# DE-260924.net
KiCad netlist of a schematic drawn in Altium Designer
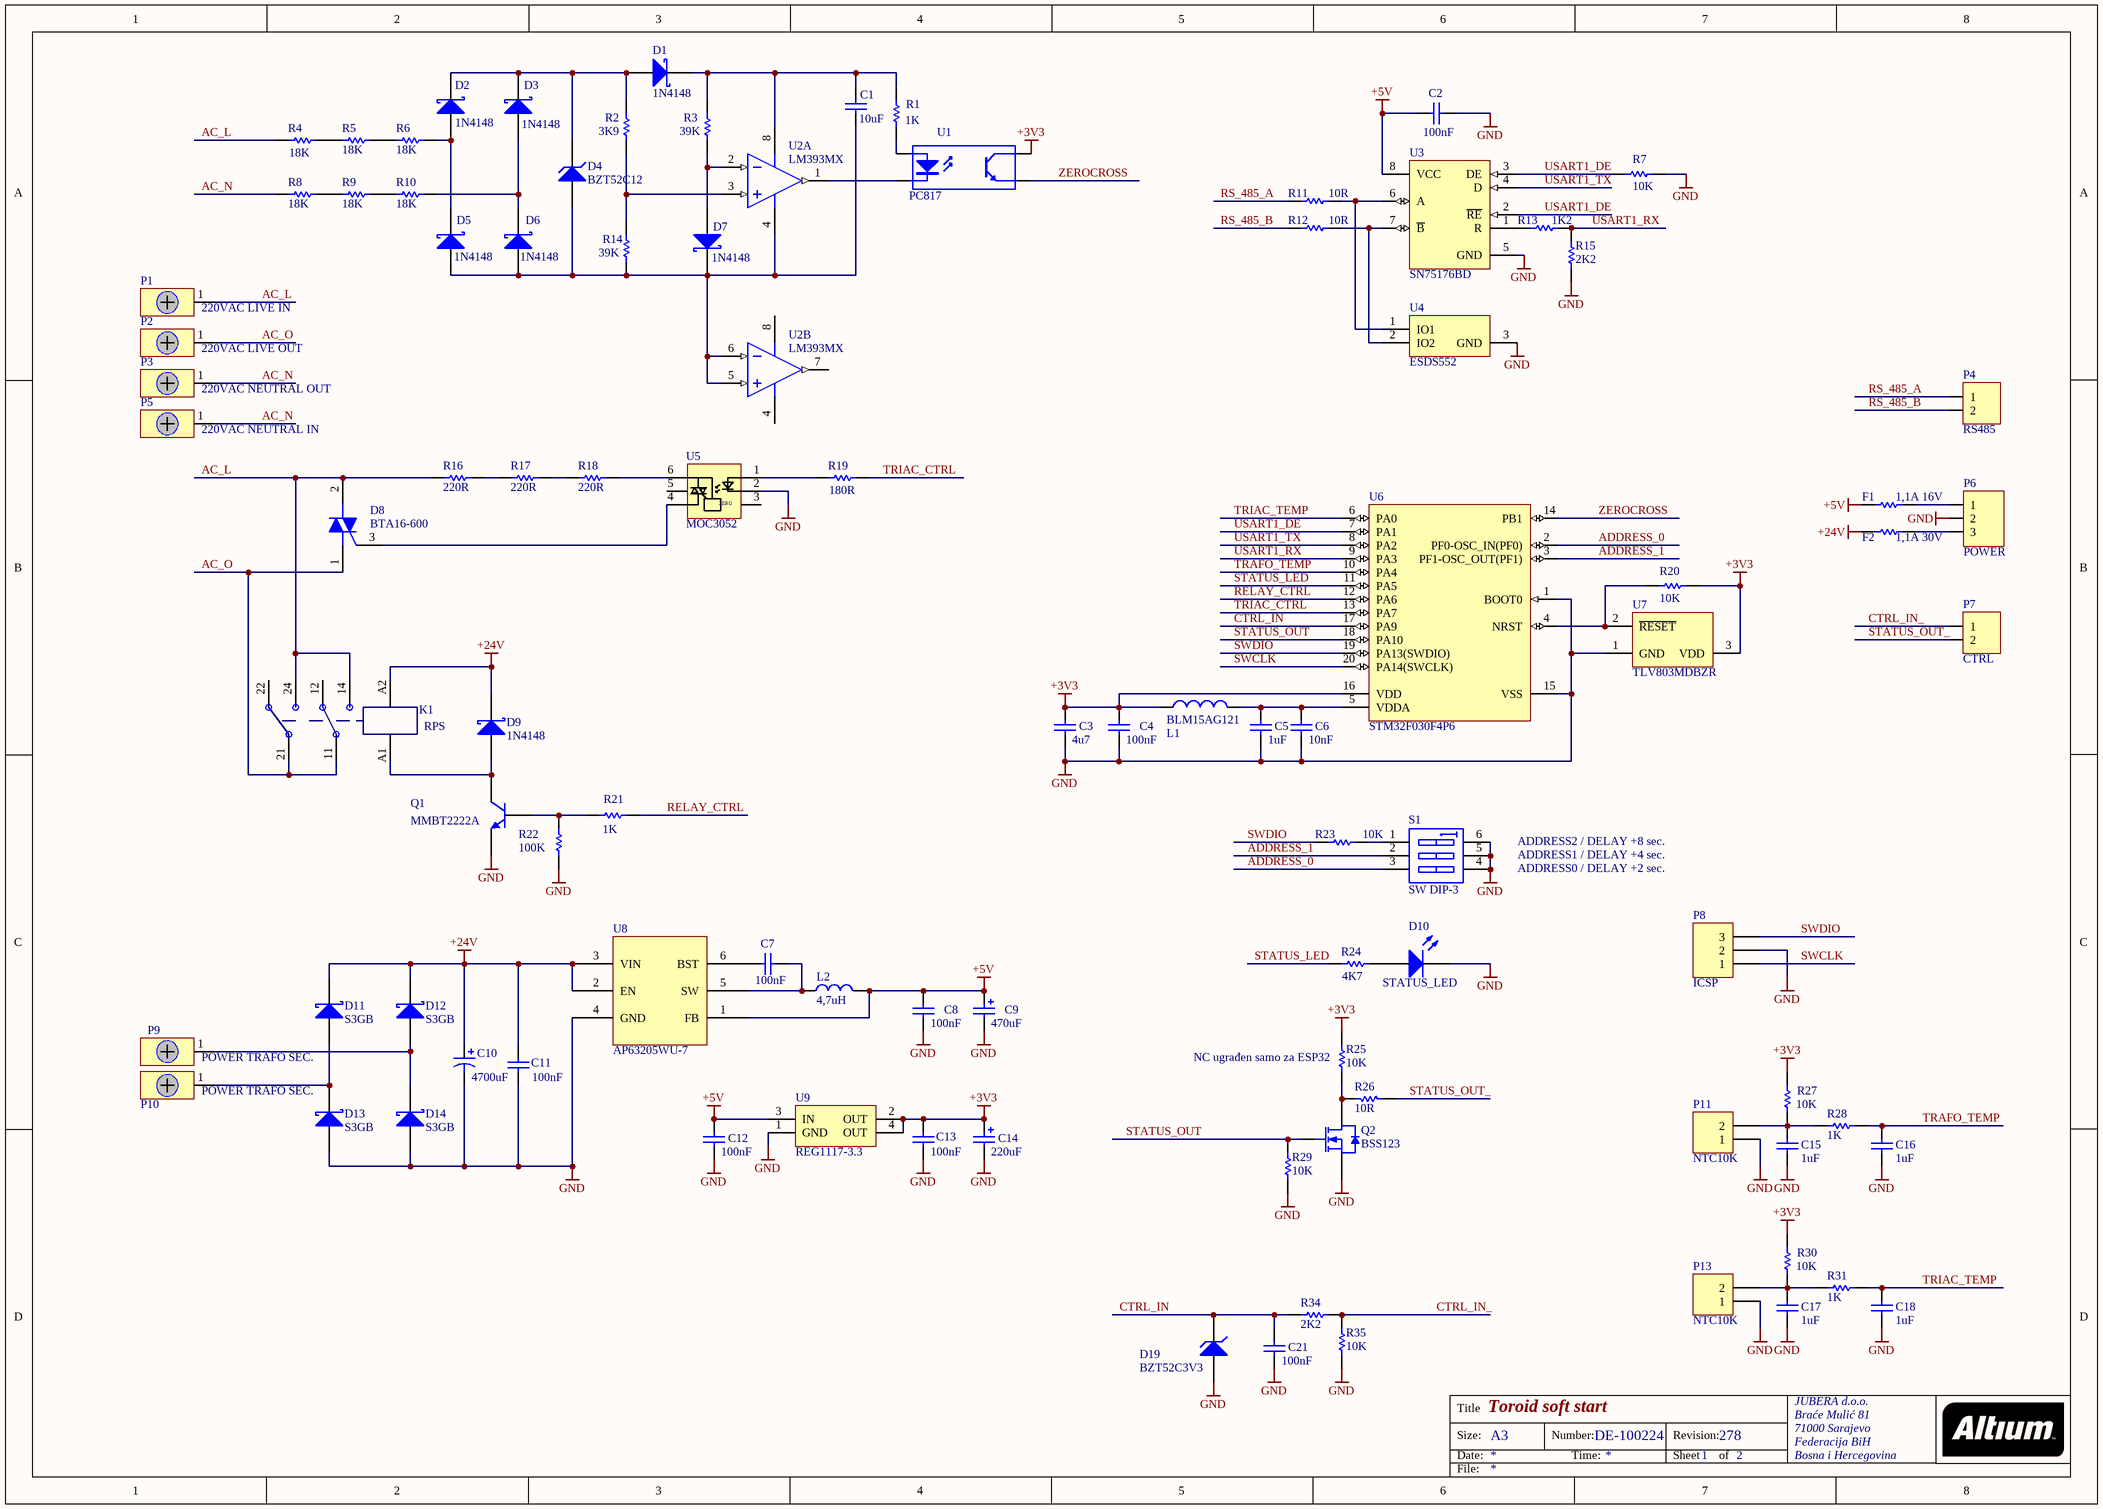
[diagram p0: DE-260924.SchDoc]

(export (version "E")
  (design (tool "Eeschema 10.0.6"))
  (components
    (comp (ref "C1")
      (value "10uF")
      (footprint "0805")
      (description "Ceramic Chip Capacitor - Standard")
      (fields (field (name "PUBLISHER") "Altium Limited"))
      (libsource (lib "DE-260924") (part "C0805"))
    )
    (comp (ref "C2")
      (value "100nF")
      (footprint "0603")
      (description "Ceramic Chip Capacitor - Standard")
      (fields (field (name "PUBLISHER") "Altium Limited"))
      (libsource (lib "DE-260924") (part "C0603"))
    )
    (comp (ref "C3")
      (value "4u7")
      (footprint "0805")
      (description "Ceramic Chip Capacitor - Standard")
      (fields (field (name "Comment") "C0805") (field (name "PUBLISHER") "Altium Limited"))
      (libsource (lib "DE-260924") (part "C0805"))
    )
    (comp (ref "C4")
      (value "100nF")
      (footprint "0603")
      (description "Ceramic Chip Capacitor - Standard")
      (fields (field (name "Comment") "C0603") (field (name "PUBLISHER") "Altium Limited"))
      (libsource (lib "DE-260924") (part "C0603"))
    )
    (comp (ref "C5")
      (value "1uF")
      (footprint "0603")
      (description "Ceramic Chip Capacitor - Standard")
      (fields (field (name "Comment") "C0603") (field (name "PUBLISHER") "Altium Limited"))
      (libsource (lib "DE-260924") (part "C0603"))
    )
    (comp (ref "C6")
      (value "10nF")
      (footprint "0603")
      (description "Ceramic Chip Capacitor - Standard")
      (fields (field (name "Comment") "C0603") (field (name "PUBLISHER") "Altium Limited"))
      (libsource (lib "DE-260924") (part "C0603"))
    )
    (comp (ref "C7")
      (value "100nF")
      (footprint "0603")
      (description "Ceramic Chip Capacitor - 25V")
      (fields (field (name "PUBLISHER") "Altium Limited"))
      (libsource (lib "DE-260924") (part "C0603"))
    )
    (comp (ref "C8")
      (value "100nF")
      (footprint "0603")
      (description "Ceramic Chip Capacitor - 25V")
      (fields (field (name "Comment") "C0603") (field (name "PUBLISHER") "Altium Limited"))
      (libsource (lib "DE-260924") (part "C0603"))
    )
    (comp (ref "C9")
      (value "470uF")
      (footprint "SMD,D6.3xL7.7mm Aluminum Electrolytic Capacitors")
      (description "470uF 16V 185mA@120Hz ±20% SMD,D6.3xL7.7mm Aluminum Electrolytic Capacitors - SMD ROHS")
      (fields (field (name "PUBLISHER") "Altium Limited"))
      (libsource (lib "DE-260924") (part "ROQANG RVT1C471M0607"))
    )
    (comp (ref "C10")
      (value "4700uF")
      (footprint "CAPPR5-13X25")
      (description "Aluminum Electrolytic Capacitor, Radial Style with Long Leads: 4700uF, 10V")
      (fields (field (name "PUBLISHER") "Altium Limited"))
      (libsource (lib "Vishay Roederstein Electrolytic Radial-Lead Capacitor") (part "EKA00GG447C00"))
    )
    (comp (ref "C11")
      (value "100nF")
      (footprint "0603")
      (description "Ceramic Chip Capacitor - Standard")
      (fields (field (name "PUBLISHER") "Altium Limited"))
      (libsource (lib "DE-260924") (part "C0603"))
    )
    (comp (ref "C12")
      (value "100nF")
      (footprint "0603")
      (description "Ceramic Chip Capacitor - 25V")
      (fields (field (name "PUBLISHER") "Altium Limited"))
      (libsource (lib "DE-260924") (part "C0603"))
    )
    (comp (ref "C13")
      (value "100nF")
      (footprint "0603")
      (description "Ceramic Chip Capacitor - Standard")
      (fields (field (name "PUBLISHER") "Altium Limited"))
      (libsource (lib "DE-260924") (part "C0603"))
    )
    (comp (ref "C14")
      (value "220uF")
      (footprint "SMD,D6.3xL7.7mm Aluminum Electrolytic Capacitors")
      (description "220uF 16V 110mA@120Hz ±20% SMD,D6.3xL7.7mm Aluminum Electrolytic Capacitors - SMD ROHS")
      (fields (field (name "PUBLISHER") "Altium Limited"))
      (libsource (lib "DE-260924") (part "ROQANG VT1C221M0607"))
    )
    (comp (ref "C15")
      (value "1uF")
      (footprint "0603")
      (description "Ceramic Chip Capacitor - Standard")
      (fields (field (name "PUBLISHER") "Altium Limited"))
      (libsource (lib "DE-260924") (part "C0603"))
    )
    (comp (ref "C16")
      (value "1uF")
      (footprint "0603")
      (description "Ceramic Chip Capacitor - Standard")
      (fields (field (name "PUBLISHER") "Altium Limited"))
      (libsource (lib "DE-260924") (part "C0603"))
    )
    (comp (ref "C17")
      (value "1uF")
      (footprint "0603")
      (description "Ceramic Chip Capacitor - Standard")
      (fields (field (name "PUBLISHER") "Altium Limited"))
      (libsource (lib "DE-260924") (part "C0603"))
    )
    (comp (ref "C18")
      (value "1uF")
      (footprint "0603")
      (description "Ceramic Chip Capacitor - Standard")
      (fields (field (name "PUBLISHER") "Altium Limited"))
      (libsource (lib "DE-260924") (part "C0603"))
    )
    (comp (ref "C21")
      (value "100nF")
      (footprint "0603")
      (description "Ceramic Chip Capacitor - Standard")
      (fields (field (name "PUBLISHER") "Altium Limited"))
      (libsource (lib "DE-260924") (part "C0603"))
    )
    (comp (ref "D1")
      (value "1N4148")
      (footprint "SOD323")
      (description "Schottky Barrier Diode")
      (fields (field (name "PUBLISHER") "Altium Limited"))
      (libsource (lib "DE-100224") (part "1PS76SB10"))
    )
    (comp (ref "D2")
      (value "1N4148")
      (footprint "SOD323")
      (description "Schottky Barrier Diode")
      (fields (field (name "PUBLISHER") "Altium Limited"))
      (libsource (lib "DE-100224") (part "1PS76SB10"))
    )
    (comp (ref "D3")
      (value "1N4148")
      (footprint "SOD323")
      (description "Schottky Barrier Diode")
      (fields (field (name "PUBLISHER") "Altium Limited"))
      (libsource (lib "DE-100224") (part "1PS76SB10"))
    )
    (comp (ref "D4")
      (value "BZT52C12")
      (footprint "SOD-123")
      (description "Surface Mount Zener Diode")
      (fields (field (name "PUBLISHER") "Altium Limited"))
      (libsource (lib "Vishay Lite-On Discrete Diode") (part "BZT52C12"))
    )
    (comp (ref "D5")
      (value "1N4148")
      (footprint "SOD323")
      (description "Schottky Barrier Diode")
      (fields (field (name "PUBLISHER") "Altium Limited"))
      (libsource (lib "DE-100224") (part "1PS76SB10"))
    )
    (comp (ref "D6")
      (value "1N4148")
      (footprint "SOD323")
      (description "Schottky Barrier Diode")
      (fields (field (name "PUBLISHER") "Altium Limited"))
      (libsource (lib "DE-100224") (part "1PS76SB10"))
    )
    (comp (ref "D7")
      (value "1N4148")
      (footprint "SOD323")
      (description "Schottky Barrier Diode")
      (fields (field (name "PUBLISHER") "Altium Limited"))
      (libsource (lib "DE-100224") (part "1PS76SB10"))
    )
    (comp (ref "D8")
      (value "BTA16-600")
      (footprint "ONSC-TO-220-3-221A-07")
      (description "Triacs, Silicon Bidirectional Thyristor, 3-Pin TO-220, Pb-Free, Tube")
      (fields (field (name "MANUFACTURER") "On Semiconductor") (field (name "PARTNUMBER") "BTA08-600BW3G"))
      (libsource (lib "DE-100224") (part "BTA08-600BW3G"))
    )
    (comp (ref "D9")
      (value "1N4148")
      (footprint "SOD323")
      (description "Schottky Barrier Diode")
      (fields (field (name "PUBLISHER") "Altium Limited"))
      (libsource (lib "DE-100224") (part "1PS76SB10"))
    )
    (comp (ref "D10")
      (value "STATUS_LED")
      (footprint "1.6X0.8X0.8")
      (description "Blue Surface Mount Chip LED, Blue")
      (fields (field (name "PUBLISHER") "Altium Limited"))
      (libsource (lib "DE-160724") (part "HSMB-C190"))
    )
    (comp (ref "D11")
      (value "S3GB")
      (footprint "SMB")
      (description "Schottky Diode")
      (fields (field (name "PUBLISHER") "Altium Limited"))
      (libsource (lib "Miscellaneous Devices") (part "D Schottky"))
    )
    (comp (ref "D12")
      (value "S3GB")
      (footprint "SMB")
      (description "Schottky Diode")
      (fields (field (name "PUBLISHER") "Altium Limited"))
      (libsource (lib "Miscellaneous Devices") (part "D Schottky"))
    )
    (comp (ref "D13")
      (value "S3GB")
      (footprint "SMB")
      (description "Schottky Diode")
      (fields (field (name "PUBLISHER") "Altium Limited"))
      (libsource (lib "Miscellaneous Devices") (part "D Schottky"))
    )
    (comp (ref "D14")
      (value "S3GB")
      (footprint "SMB")
      (description "Schottky Diode")
      (fields (field (name "PUBLISHER") "Altium Limited"))
      (libsource (lib "Miscellaneous Devices") (part "D Schottky"))
    )
    (comp (ref "D19")
      (value "BZT52C3V3")
      (footprint "SOD-123")
      (description "Surface Mount Zener Diode")
      (fields (field (name "PUBLISHER") "Altium Limited"))
      (libsource (lib "Vishay Lite-On Discrete Diode") (part "BZT52C3V3"))
    )
    (comp (ref "F1")
      (value "1,1A 16V")
      (footprint "12-1812")
      (description "Retriggerable SMD fuse 1,1A, 16V")
      (fields (field (name "PUBLISHER") "Altium Limited"))
      (libsource (lib "DE-260924") (part "ERJL12"))
    )
    (comp (ref "F2")
      (value "1,1A 30V")
      (footprint "12-1812")
      (description "Retriggerable SMD fuse 1,1A, 16V")
      (fields (field (name "PUBLISHER") "Altium Limited"))
      (libsource (lib "DE-260924") (part "ERJL12"))
    )
    (comp (ref "K1")
      (value "RPS")
      (footprint "RPS 2CO 8A 24V")
      (libsource (lib "DE-260924") (part "PCB relay 2CO, 8A, 24VDC, RPS serie 5mm"))
    )
    (comp (ref "L1")
      (value "BLM15AG121")
      (footprint "0603")
      (description "SMD chip inductor")
      (fields (field (name "PUBLISHER") "Altium Limited"))
      (libsource (lib "DE-260924") (part "Chip inductor"))
    )
    (comp (ref "L2")
      (value "4,7uH")
      (footprint "XRNR4030-4.7uH/M")
      (libsource (lib "DE-260924") (part "Inductor"))
    )
    (comp (ref "P1")
      (value "220VAC LIVE IN")
      (footprint "WIRE PAD")
      (libsource (lib "DE-260924") (part "Wire Lug"))
    )
    (comp (ref "P2")
      (value "220VAC LIVE OUT")
      (footprint "WIRE PAD")
      (libsource (lib "DE-260924") (part "Wire Lug"))
    )
    (comp (ref "P3")
      (value "220VAC NEUTRAL OUT")
      (footprint "WIRE PAD")
      (libsource (lib "DE-260924") (part "Wire Lug"))
    )
    (comp (ref "P4")
      (value "RS485")
      (footprint "TERMINAL BLOK 2")
      (description "Terminal blok konektor 3,5 mm")
      (libsource (lib "DE-160724") (part "TERMINAL BLOK 2"))
    )
    (comp (ref "P5")
      (value "220VAC NEUTRAL IN")
      (footprint "WIRE PAD")
      (libsource (lib "DE-260924") (part "Wire Lug"))
    )
    (comp (ref "P6")
      (value "POWER")
      (footprint "TERMINAL BLOK 3")
      (description "3 pinski terminal blok konektor")
      (libsource (lib "DE-100224") (part "TERMINAL BLOK 3"))
    )
    (comp (ref "P7")
      (value "CTRL")
      (footprint "TERMINAL BLOK 2")
      (description "Terminal blok konektor 3,5 mm")
      (libsource (lib "DE-160724") (part "TERMINAL BLOK 2"))
    )
    (comp (ref "P8")
      (value "ICSP")
      (footprint "HDR1X3")
      (description "Header, 3-Pin")
      (fields (field (name "PUBLISHER") "Altium Limited"))
      (libsource (lib "Miscellaneous Connectors") (part "Header 3"))
    )
    (comp (ref "P9")
      (value "POWER TRAFO SEC.")
      (footprint "WIRE PAD")
      (libsource (lib "DE-260924") (part "Wire Lug"))
    )
    (comp (ref "P10")
      (value "POWER TRAFO SEC.")
      (footprint "WIRE PAD")
      (libsource (lib "DE-260924") (part "Wire Lug"))
    )
    (comp (ref "P11")
      (value "NTC10K")
      (footprint "HDR1X2")
      (description "Header, 2-Pin")
      (fields (field (name "PUBLISHER") "Altium Limited"))
      (libsource (lib "Miscellaneous Connectors") (part "Header 2"))
    )
    (comp (ref "P13")
      (value "NTC10K")
      (footprint "HDR1X2")
      (description "Header, 2-Pin")
      (fields (field (name "PUBLISHER") "Altium Limited"))
      (libsource (lib "Miscellaneous Connectors") (part "Header 2"))
    )
    (comp (ref "Q1")
      (value "MMBT2222A")
      (footprint "SOT23_N")
      (description "NPN General-purpose Transistor")
      (fields (field (name "PUBLISHER") "Altium Limited"))
      (libsource (lib "DE-100224") (part "BC817"))
    )
    (comp (ref "Q2")
      (value "BSS123")
      (footprint "SOT23_N")
      (description "N-channel Enhancement Mode Vertical D-MOSFET")
      (fields (field (name "PUBLISHER") "Altium Limited"))
      (libsource (lib "DE-260924") (part "BSS123"))
    )
    (comp (ref "R1")
      (value "1K")
      (footprint "ERA-0603")
      (fields (field (name "PUBLISHER") "Altium Limited"))
      (libsource (lib "DE-100224") (part "ERAV"))
    )
    (comp (ref "R2")
      (value "3K9")
      (footprint "ERA-0603")
      (fields (field (name "PUBLISHER") "Altium Limited"))
      (libsource (lib "DE-100224") (part "ERAV"))
    )
    (comp (ref "R3")
      (value "39K")
      (footprint "ERA-0603")
      (fields (field (name "PUBLISHER") "Altium Limited"))
      (libsource (lib "DE-100224") (part "ERAV"))
    )
    (comp (ref "R4")
      (value "18K")
      (footprint "ERA-0805")
      (fields (field (name "Comment") "0805") (field (name "PUBLISHER") "Altium Limited"))
      (libsource (lib "DE-100224") (part "ERAS"))
    )
    (comp (ref "R5")
      (value "18K")
      (footprint "ERA-0805")
      (fields (field (name "PUBLISHER") "Altium Limited"))
      (libsource (lib "DE-100224") (part "ERAS"))
    )
    (comp (ref "R6")
      (value "18K")
      (footprint "ERA-0805")
      (fields (field (name "PUBLISHER") "Altium Limited"))
      (libsource (lib "DE-100224") (part "ERAS"))
    )
    (comp (ref "R7")
      (value "10K")
      (footprint "ERA-0603")
      (fields (field (name "PUBLISHER") "Altium Limited"))
      (libsource (lib "DE-150824") (part "ERAV"))
    )
    (comp (ref "R8")
      (value "18K")
      (footprint "ERA-0805")
      (fields (field (name "PUBLISHER") "Altium Limited"))
      (libsource (lib "DE-100224") (part "ERAS"))
    )
    (comp (ref "R9")
      (value "18K")
      (footprint "ERA-0805")
      (fields (field (name "PUBLISHER") "Altium Limited"))
      (libsource (lib "DE-100224") (part "ERAS"))
    )
    (comp (ref "R10")
      (value "18K")
      (footprint "ERA-0805")
      (fields (field (name "PUBLISHER") "Altium Limited"))
      (libsource (lib "DE-100224") (part "ERAS"))
    )
    (comp (ref "R11")
      (value "10R")
      (footprint "ERA-0805")
      (fields (field (name "PUBLISHER") "Altium Limited"))
      (libsource (lib "DE-150824") (part "ERAS"))
    )
    (comp (ref "R12")
      (value "10R")
      (footprint "ERA-0805")
      (fields (field (name "PUBLISHER") "Altium Limited"))
      (libsource (lib "DE-150824") (part "ERAS"))
    )
    (comp (ref "R13")
      (value "1K2")
      (footprint "ERA-0603")
      (fields (field (name "PUBLISHER") "Altium Limited"))
      (libsource (lib "DE-150824") (part "ERAV"))
    )
    (comp (ref "R14")
      (value "39K")
      (footprint "ERA-0603")
      (fields (field (name "PUBLISHER") "Altium Limited"))
      (libsource (lib "DE-100224") (part "ERAV"))
    )
    (comp (ref "R15")
      (value "2K2")
      (footprint "ERA-0603")
      (fields (field (name "PUBLISHER") "Altium Limited"))
      (libsource (lib "DE-150824") (part "ERAV"))
    )
    (comp (ref "R16")
      (value "220R")
      (footprint "ERA-0805")
      (fields (field (name "PUBLISHER") "Altium Limited"))
      (libsource (lib "DE-100224") (part "ERAS"))
    )
    (comp (ref "R17")
      (value "220R")
      (footprint "ERA-0805")
      (fields (field (name "PUBLISHER") "Altium Limited"))
      (libsource (lib "DE-100224") (part "ERAS"))
    )
    (comp (ref "R18")
      (value "220R")
      (footprint "ERA-0805")
      (fields (field (name "PUBLISHER") "Altium Limited"))
      (libsource (lib "DE-100224") (part "ERAS"))
    )
    (comp (ref "R19")
      (value "180R")
      (footprint "ERA-0603")
      (fields (field (name "PUBLISHER") "Altium Limited"))
      (libsource (lib "DE-100224") (part "ERAV"))
    )
    (comp (ref "R20")
      (value "10K")
      (footprint "ERA-0603")
      (fields (field (name "Comment") "180R") (field (name "PUBLISHER") "Altium Limited"))
      (libsource (lib "DE-100224") (part "ERAV"))
    )
    (comp (ref "R21")
      (value "1K")
      (footprint "ERA-0603")
      (fields (field (name "PUBLISHER") "Altium Limited"))
      (libsource (lib "DE-100224") (part "ERAV"))
    )
    (comp (ref "R22")
      (value "100K")
      (footprint "ERA-0603")
      (fields (field (name "PUBLISHER") "Altium Limited"))
      (libsource (lib "DE-100224") (part "ERAV"))
    )
    (comp (ref "R23")
      (value "10K")
      (footprint "ERA-0603")
      (fields (field (name "Comment") "180R") (field (name "PUBLISHER") "Altium Limited"))
      (libsource (lib "DE-100224") (part "ERAV"))
    )
    (comp (ref "R24")
      (value "4K7")
      (footprint "ERA-0603")
      (fields (field (name "Comment") "180R") (field (name "PUBLISHER") "Altium Limited"))
      (libsource (lib "DE-100224") (part "ERAV"))
    )
    (comp (ref "R25")
      (value "10K")
      (footprint "ERA-0603")
      (fields (field (name "Comment") "180R") (field (name "PUBLISHER") "Altium Limited"))
      (libsource (lib "DE-100224") (part "ERAV"))
    )
    (comp (ref "R26")
      (value "10R")
      (footprint "ERA-0603")
      (fields (field (name "PUBLISHER") "Altium Limited"))
      (libsource (lib "DE-280817") (part "ERA6Y"))
    )
    (comp (ref "R27")
      (value "10K")
      (footprint "ERA-0603")
      (fields (field (name "PUBLISHER") "Altium Limited"))
      (libsource (lib "DE-100224") (part "ERAV"))
    )
    (comp (ref "R28")
      (value "1K")
      (footprint "ERA-0603")
      (fields (field (name "PUBLISHER") "Altium Limited"))
      (libsource (lib "DE-100224") (part "ERAV"))
    )
    (comp (ref "R29")
      (value "10K")
      (footprint "ERA-0603")
      (fields (field (name "Comment") "180R") (field (name "PUBLISHER") "Altium Limited"))
      (libsource (lib "DE-100224") (part "ERAV"))
    )
    (comp (ref "R30")
      (value "10K")
      (footprint "ERA-0603")
      (fields (field (name "PUBLISHER") "Altium Limited"))
      (libsource (lib "DE-100224") (part "ERAV"))
    )
    (comp (ref "R31")
      (value "1K")
      (footprint "ERA-0603")
      (fields (field (name "PUBLISHER") "Altium Limited"))
      (libsource (lib "DE-100224") (part "ERAV"))
    )
    (comp (ref "R34")
      (value "2K2")
      (footprint "ERA-0603")
      (fields (field (name "Comment") "180R") (field (name "PUBLISHER") "Altium Limited"))
      (libsource (lib "DE-100224") (part "ERAV"))
    )
    (comp (ref "R35")
      (value "10K")
      (footprint "ERA-0603")
      (fields (field (name "Comment") "180R") (field (name "PUBLISHER") "Altium Limited"))
      (libsource (lib "DE-100224") (part "ERAV"))
    )
    (comp (ref "S1")
      (value "SW DIP-3")
      (footprint "DIP-6")
      (description "DIP Switch, 3 Position, SPST")
      (fields (field (name "PUBLISHER") "Altium Limited"))
      (libsource (lib "Miscellaneous Devices") (part "SW DIP-3"))
    )
    (comp (ref "U1")
      (value "PC817")
      (footprint "DIP-4")
      (description "4-Pin Phototransistor Optocoupler")
      (fields (field (name "PUBLISHER") "Altium Limited"))
      (libsource (lib "DE-100224") (part "PC817"))
    )
    (comp (ref "U2")
      (value "LM393MX")
      (footprint "M08A_N")
      (description "Low Power Low Offset Voltage Dual Comparator, 8-pin Narrow SOIC")
      (fields (field (name "MANUFACTURER") "National Semiconductor"))
      (libsource (lib "National Semiconductor Comparator") (part "LM393MX"))
    )
    (comp (ref "U3")
      (value "SN75176BD")
      (footprint "D008_N")
      (description "Differential Bus Transceiver")
      (fields (field (name "PUBLISHER") "Altium Limited"))
      (libsource (lib "DE-150824") (part "SN75176BD"))
    )
    (comp (ref "U4")
      (value "ESDS552")
      (footprint "DCK3_N")
      (fields (field (name "MANUFACTURER") "Texas Instruments") (field (name "PARTNUMBER") "TPD2E007DCKR"))
      (libsource (lib "TI Interface ESD EMI Protection") (part "TPD2E007DCKR"))
    )
    (comp (ref "U5")
      (value "MOC3052")
      (footprint "DIP6")
      (description "Zero-Cross Optoisolator Triac Driver")
      (libsource (lib "DE-100224") (part "MOC3081"))
    )
    (comp (ref "U6")
      (value "STM32F030F4P6")
      (footprint "STM-TSSOP20_N")
      (libsource (lib "STMicroelectronics STM32 F0") (part "STM32F030F4P6"))
    )
    (comp (ref "U7")
      (value "TLV803MDBZR")
      (footprint "DBZ3_N")
      (fields (field (name "MANUFACTURER") "Texas Instruments"))
      (libsource (lib "TI Power Management Supervisor and Reset IC") (part "TLV803MDBZR"))
    )
    (comp (ref "U8")
      (value "AP63205WU-7")
      (footprint "TSOT-26")
      (description "2A synchronous  buck converter")
      (libsource (lib "DE-250624") (part "AP63200"))
    )
    (comp (ref "U9")
      (value "REG1117-3.3")
      (footprint "ZZ311")
      (description "800mA and 1A Low Dropout Positive Regulator 2.85V, 3.3V, 5V, and Adjustable")
      (fields (field (name "PUBLISHER") "Altium Limited"))
      (libsource (lib "DE-251215") (part "REG1117-3.3"))
    )
  )
  (nets
    (net (code "1") (name "+3V3") (class "Default")
      (node (ref "C13") (pin "2") (pinfunction "2_2") (pintype "passive"))
      (node (ref "C14") (pin "1") (pinfunction "1_1") (pintype "passive"))
      (node (ref "C3") (pin "2") (pinfunction "2_2") (pintype "passive"))
      (node (ref "C4") (pin "2") (pinfunction "2_2") (pintype "passive"))
      (node (ref "L1") (pin "1") (pinfunction "1_1") (pintype "passive"))
      (node (ref "R20") (pin "1") (pinfunction "1_1") (pintype "passive"))
      (node (ref "R25") (pin "1") (pinfunction "1_1") (pintype "passive"))
      (node (ref "R27") (pin "2") (pinfunction "2_2") (pintype "passive"))
      (node (ref "R30") (pin "2") (pinfunction "2_2") (pintype "passive"))
      (node (ref "U1") (pin "4") (pinfunction "C_4") (pintype "passive"))
      (node (ref "U6") (pin "16") (pinfunction "VDD_16") (pintype "power_in"))
      (node (ref "U7") (pin "3") (pinfunction "VDD_3") (pintype "power_in"))
      (node (ref "U9") (pin "2") (pinfunction "OUT_2") (pintype "power_in"))
      (node (ref "U9") (pin "4") (pinfunction "OUT_4") (pintype "power_in"))
    )
    (net (code "2") (name "+5V") (class "Default")
      (node (ref "C12") (pin "2") (pinfunction "2_2") (pintype "passive"))
      (node (ref "C2") (pin "2") (pinfunction "2_2") (pintype "passive"))
      (node (ref "C8") (pin "2") (pinfunction "2_2") (pintype "passive"))
      (node (ref "C9") (pin "1") (pinfunction "1_1") (pintype "passive"))
      (node (ref "F1") (pin "1") (pinfunction "1_1") (pintype "passive"))
      (node (ref "L2") (pin "1") (pinfunction "1_1") (pintype "passive"))
      (node (ref "U3") (pin "8") (pinfunction "VCC_8") (pintype "power_in"))
      (node (ref "U8") (pin "1") (pinfunction "FB_1") (pintype "passive"))
      (node (ref "U9") (pin "3") (pinfunction "IN_3") (pintype "power_in"))
    )
    (net (code "3") (name "+24V") (class "Default")
      (node (ref "C10") (pin "1") (pinfunction "1_1") (pintype "passive"))
      (node (ref "C11") (pin "2") (pinfunction "2_2") (pintype "passive"))
      (node (ref "D11") (pin "2") (pinfunction "K_2") (pintype "passive"))
      (node (ref "D12") (pin "2") (pinfunction "K_2") (pintype "passive"))
      (node (ref "D9") (pin "1") (pinfunction "K_1") (pintype "passive"))
      (node (ref "F2") (pin "1") (pinfunction "1_1") (pintype "passive"))
      (node (ref "K1") (pin "A2") (pinfunction "2_A2") (pintype "passive"))
      (node (ref "U8") (pin "2") (pinfunction "EN_2") (pintype "passive"))
      (node (ref "U8") (pin "3") (pinfunction "VIN_3") (pintype "power_in"))
    )
    (net (code "4") (name "/AC_L") (class "Default")
      (node (ref "D8") (pin "2") (pinfunction "MT2_2") (pintype "passive"))
      (node (ref "K1") (pin "14") (pinfunction "4_14") (pintype "passive"))
      (node (ref "K1") (pin "24") (pinfunction "4_24") (pintype "passive"))
      (node (ref "P1") (pin "1") (pinfunction "1_1") (pintype "passive"))
      (node (ref "R16") (pin "1") (pinfunction "1_1") (pintype "passive"))
      (node (ref "R4") (pin "1") (pinfunction "1_1") (pintype "passive"))
    )
    (net (code "5") (name "/AC_N") (class "Default")
      (node (ref "P3") (pin "1") (pinfunction "1_1") (pintype "passive"))
      (node (ref "P5") (pin "1") (pinfunction "1_1") (pintype "passive"))
      (node (ref "R8") (pin "1") (pinfunction "1_1") (pintype "passive"))
    )
    (net (code "6") (name "/AC_O") (class "Default")
      (node (ref "D8") (pin "1") (pinfunction "MT1_1") (pintype "passive"))
      (node (ref "K1") (pin "11") (pinfunction "3_11") (pintype "passive"))
      (node (ref "K1") (pin "21") (pinfunction "3_21") (pintype "passive"))
      (node (ref "P2") (pin "1") (pinfunction "1_1") (pintype "passive"))
    )
    (net (code "7") (name "/ADDRESS_0") (class "Default")
      (node (ref "S1") (pin "3") (pinfunction "A3_3") (pintype "passive"))
      (node (ref "U6") (pin "2") (pinfunction "PF0-OSC_IN(PF0)_2") (pintype "bidirectional"))
    )
    (net (code "8") (name "/ADDRESS_1") (class "Default")
      (node (ref "S1") (pin "2") (pinfunction "A2_2") (pintype "passive"))
      (node (ref "U6") (pin "3") (pinfunction "PF1-OSC_OUT(PF1)_3") (pintype "bidirectional"))
    )
    (net (code "9") (name "/CTRL_IN") (class "Default")
      (node (ref "C21") (pin "2") (pinfunction "2_2") (pintype "passive"))
      (node (ref "D19") (pin "2") (pinfunction "K_2") (pintype "passive"))
      (node (ref "R34") (pin "1") (pinfunction "1_1") (pintype "passive"))
      (node (ref "U6") (pin "17") (pinfunction "PA9_17") (pintype "bidirectional"))
    )
    (net (code "10") (name "/CTRL_IN_") (class "Default")
      (node (ref "P7") (pin "1") (pinfunction "1_1") (pintype "passive"))
      (node (ref "R34") (pin "2") (pinfunction "2_2") (pintype "passive"))
      (node (ref "R35") (pin "1") (pinfunction "1_1") (pintype "passive"))
    )
    (net (code "11") (name "/RELAY_CTRL") (class "Default")
      (node (ref "R21") (pin "1") (pinfunction "1_1") (pintype "passive"))
      (node (ref "U6") (pin "12") (pinfunction "PA6_12") (pintype "bidirectional"))
    )
    (net (code "12") (name "/RS_485_A") (class "Default")
      (node (ref "P4") (pin "1") (pinfunction "1_1") (pintype "passive"))
      (node (ref "R11") (pin "1") (pinfunction "1_1") (pintype "passive"))
    )
    (net (code "13") (name "/RS_485_B") (class "Default")
      (node (ref "P4") (pin "2") (pinfunction "2_2") (pintype "passive"))
      (node (ref "R12") (pin "1") (pinfunction "1_1") (pintype "passive"))
    )
    (net (code "14") (name "/STATUS_LED") (class "Default")
      (node (ref "R24") (pin "2") (pinfunction "2_2") (pintype "passive"))
      (node (ref "U6") (pin "11") (pinfunction "PA5_11") (pintype "bidirectional"))
    )
    (net (code "15") (name "/STATUS_OUT") (class "Default")
      (node (ref "Q2") (pin "1") (pinfunction "G_1") (pintype "passive"))
      (node (ref "R29") (pin "1") (pinfunction "1_1") (pintype "passive"))
      (node (ref "U6") (pin "18") (pinfunction "PA10_18") (pintype "bidirectional"))
    )
    (net (code "16") (name "/STATUS_OUT_") (class "Default")
      (node (ref "P7") (pin "2") (pinfunction "2_2") (pintype "passive"))
      (node (ref "R26") (pin "2") (pinfunction "2_2") (pintype "passive"))
    )
    (net (code "17") (name "/SWCLK") (class "Default")
      (node (ref "P8") (pin "1") (pinfunction "1_1") (pintype "passive"))
      (node (ref "U6") (pin "20") (pinfunction "PA14(SWCLK)_20") (pintype "bidirectional"))
    )
    (net (code "18") (name "/SWDIO") (class "Default")
      (node (ref "P8") (pin "3") (pinfunction "3_3") (pintype "passive"))
      (node (ref "R23") (pin "2") (pinfunction "2_2") (pintype "passive"))
      (node (ref "U6") (pin "19") (pinfunction "PA13(SWDIO)_19") (pintype "bidirectional"))
    )
    (net (code "19") (name "/TRAFO_TEMP") (class "Default")
      (node (ref "C16") (pin "1") (pinfunction "1_1") (pintype "passive"))
      (node (ref "R28") (pin "1") (pinfunction "1_1") (pintype "passive"))
      (node (ref "U6") (pin "10") (pinfunction "PA4_10") (pintype "bidirectional"))
    )
    (net (code "20") (name "/TRIAC_CTRL") (class "Default")
      (node (ref "R19") (pin "1") (pinfunction "1_1") (pintype "passive"))
      (node (ref "U6") (pin "13") (pinfunction "PA7_13") (pintype "bidirectional"))
    )
    (net (code "21") (name "/TRIAC_TEMP") (class "Default")
      (node (ref "C18") (pin "1") (pinfunction "1_1") (pintype "passive"))
      (node (ref "R31") (pin "1") (pinfunction "1_1") (pintype "passive"))
      (node (ref "U6") (pin "6") (pinfunction "PA0_6") (pintype "bidirectional"))
    )
    (net (code "22") (name "/USART1_DE") (class "Default")
      (node (ref "R7") (pin "1") (pinfunction "1_1") (pintype "passive"))
      (node (ref "U3") (pin "2") (pinfunction "~{RE}_2") (pintype "input"))
      (node (ref "U3") (pin "3") (pinfunction "DE_3") (pintype "input"))
      (node (ref "U6") (pin "7") (pinfunction "PA1_7") (pintype "bidirectional"))
    )
    (net (code "23") (name "/USART1_RX") (class "Default")
      (node (ref "R13") (pin "2") (pinfunction "2_2") (pintype "passive"))
      (node (ref "R15") (pin "2") (pinfunction "2_2") (pintype "passive"))
      (node (ref "U6") (pin "9") (pinfunction "PA3_9") (pintype "bidirectional"))
    )
    (net (code "24") (name "/USART1_TX") (class "Default")
      (node (ref "U3") (pin "4") (pinfunction "D_4") (pintype "input"))
      (node (ref "U6") (pin "8") (pinfunction "PA2_8") (pintype "bidirectional"))
    )
    (net (code "25") (name "/ZEROCROSS") (class "Default")
      (node (ref "U1") (pin "3") (pinfunction "E_3") (pintype "passive"))
      (node (ref "U6") (pin "14") (pinfunction "PB1_14") (pintype "bidirectional"))
    )
    (net (code "26") (name "GND") (class "Default")
      (node (ref "C10") (pin "2") (pinfunction "2_2") (pintype "passive"))
      (node (ref "C11") (pin "1") (pinfunction "1_1") (pintype "passive"))
      (node (ref "C12") (pin "1") (pinfunction "1_1") (pintype "passive"))
      (node (ref "C13") (pin "1") (pinfunction "1_1") (pintype "passive"))
      (node (ref "C14") (pin "2") (pinfunction "2_2") (pintype "passive"))
      (node (ref "C15") (pin "2") (pinfunction "2_2") (pintype "passive"))
      (node (ref "C16") (pin "2") (pinfunction "2_2") (pintype "passive"))
      (node (ref "C17") (pin "2") (pinfunction "2_2") (pintype "passive"))
      (node (ref "C18") (pin "2") (pinfunction "2_2") (pintype "passive"))
      (node (ref "C2") (pin "1") (pinfunction "1_1") (pintype "passive"))
      (node (ref "C21") (pin "1") (pinfunction "1_1") (pintype "passive"))
      (node (ref "C3") (pin "1") (pinfunction "1_1") (pintype "passive"))
      (node (ref "C4") (pin "1") (pinfunction "1_1") (pintype "passive"))
      (node (ref "C5") (pin "1") (pinfunction "1_1") (pintype "passive"))
      (node (ref "C6") (pin "1") (pinfunction "1_1") (pintype "passive"))
      (node (ref "C8") (pin "1") (pinfunction "1_1") (pintype "passive"))
      (node (ref "C9") (pin "2") (pinfunction "2_2") (pintype "passive"))
      (node (ref "D10") (pin "2") (pinfunction "K_2") (pintype "passive"))
      (node (ref "D13") (pin "1") (pinfunction "A_1") (pintype "passive"))
      (node (ref "D14") (pin "1") (pinfunction "A_1") (pintype "passive"))
      (node (ref "D19") (pin "1") (pinfunction "A_1") (pintype "passive"))
      (node (ref "P11") (pin "1") (pinfunction "1_1") (pintype "passive"))
      (node (ref "P13") (pin "1") (pinfunction "1_1") (pintype "passive"))
      (node (ref "P6") (pin "2") (pinfunction "2_2") (pintype "passive"))
      (node (ref "P8") (pin "2") (pinfunction "2_2") (pintype "passive"))
      (node (ref "Q1") (pin "2") (pinfunction "E_2") (pintype "passive"))
      (node (ref "Q2") (pin "2") (pinfunction "S_2") (pintype "passive"))
      (node (ref "R15") (pin "1") (pinfunction "1_1") (pintype "passive"))
      (node (ref "R22") (pin "1") (pinfunction "1_1") (pintype "passive"))
      (node (ref "R29") (pin "2") (pinfunction "2_2") (pintype "passive"))
      (node (ref "R35") (pin "2") (pinfunction "2_2") (pintype "passive"))
      (node (ref "R7") (pin "2") (pinfunction "2_2") (pintype "passive"))
      (node (ref "S1") (pin "4") (pinfunction "B3_4") (pintype "passive"))
      (node (ref "S1") (pin "5") (pinfunction "B2_5") (pintype "passive"))
      (node (ref "S1") (pin "6") (pinfunction "B1_6") (pintype "passive"))
      (node (ref "U3") (pin "5") (pinfunction "GND_5") (pintype "power_in"))
      (node (ref "U4") (pin "3") (pinfunction "GND_3") (pintype "power_in"))
      (node (ref "U5") (pin "2") (pinfunction "2_2") (pintype "passive"))
      (node (ref "U6") (pin "1") (pinfunction "BOOT0_1") (pintype "input"))
      (node (ref "U6") (pin "15") (pinfunction "VSS_15") (pintype "power_in"))
      (node (ref "U7") (pin "1") (pinfunction "GND_1") (pintype "power_in"))
      (node (ref "U8") (pin "4") (pinfunction "GND_4") (pintype "power_in"))
      (node (ref "U9") (pin "1") (pinfunction "GND_1") (pintype "power_in"))
    )
    (net (code "27") (name "Net-(C15-Pad1)") (class "Default")
      (node (ref "C15") (pin "1") (pinfunction "1_1") (pintype "passive"))
      (node (ref "P11") (pin "2") (pinfunction "2_2") (pintype "passive"))
      (node (ref "R27") (pin "1") (pinfunction "1_1") (pintype "passive"))
      (node (ref "R28") (pin "2") (pinfunction "2_2") (pintype "passive"))
    )
    (net (code "28") (name "Net-(C17-Pad1)") (class "Default")
      (node (ref "C17") (pin "1") (pinfunction "1_1") (pintype "passive"))
      (node (ref "P13") (pin "2") (pinfunction "2_2") (pintype "passive"))
      (node (ref "R30") (pin "1") (pinfunction "1_1") (pintype "passive"))
      (node (ref "R31") (pin "2") (pinfunction "2_2") (pintype "passive"))
    )
    (net (code "29") (name "Net-(D1-A)") (class "Default")
      (node (ref "D1") (pin "2") (pinfunction "A_2") (pintype "passive"))
      (node (ref "D2") (pin "1") (pinfunction "K_1") (pintype "passive"))
      (node (ref "D3") (pin "1") (pinfunction "K_1") (pintype "passive"))
      (node (ref "D4") (pin "2") (pinfunction "K_2") (pintype "passive"))
      (node (ref "R2") (pin "2") (pinfunction "2_2") (pintype "passive"))
    )
    (net (code "30") (name "Net-(D1-K)") (class "Default")
      (node (ref "C1") (pin "2") (pinfunction "2_2") (pintype "passive"))
      (node (ref "D1") (pin "1") (pinfunction "K_1") (pintype "passive"))
      (node (ref "R1") (pin "2") (pinfunction "2_2") (pintype "passive"))
      (node (ref "R3") (pin "2") (pinfunction "2_2") (pintype "passive"))
      (node (ref "U2") (pin "8") (pinfunction "V+_8") (pintype "power_in"))
    )
    (net (code "31") (name "Net-(D2-A)") (class "Default")
      (node (ref "D2") (pin "2") (pinfunction "A_2") (pintype "passive"))
      (node (ref "D5") (pin "1") (pinfunction "K_1") (pintype "passive"))
      (node (ref "R6") (pin "2") (pinfunction "2_2") (pintype "passive"))
    )
    (net (code "32") (name "Net-(D3-A)") (class "Default")
      (node (ref "D3") (pin "2") (pinfunction "A_2") (pintype "passive"))
      (node (ref "D6") (pin "1") (pinfunction "K_1") (pintype "passive"))
      (node (ref "R10") (pin "2") (pinfunction "2_2") (pintype "passive"))
    )
    (net (code "33") (name "Net-(D4-A)") (class "Default")
      (node (ref "C1") (pin "1") (pinfunction "1_1") (pintype "passive"))
      (node (ref "D4") (pin "1") (pinfunction "A_1") (pintype "passive"))
      (node (ref "D5") (pin "2") (pinfunction "A_2") (pintype "passive"))
      (node (ref "D6") (pin "2") (pinfunction "A_2") (pintype "passive"))
      (node (ref "D7") (pin "1") (pinfunction "K_1") (pintype "passive"))
      (node (ref "R14") (pin "1") (pinfunction "1_1") (pintype "passive"))
      (node (ref "U2") (pin "4") (pinfunction "GND_4") (pintype "power_in"))
      (node (ref "U2") (pin "5") (pinfunction "INB+_5") (pintype "input"))
      (node (ref "U2") (pin "6") (pinfunction "INB-_6") (pintype "input"))
    )
    (net (code "34") (name "Net-(D7-A)") (class "Default")
      (node (ref "D7") (pin "2") (pinfunction "A_2") (pintype "passive"))
      (node (ref "R3") (pin "1") (pinfunction "1_1") (pintype "passive"))
      (node (ref "U2") (pin "2") (pinfunction "INA-_2") (pintype "input"))
    )
    (net (code "35") (name "Net-(D8-G)") (class "Default")
      (node (ref "D8") (pin "3") (pinfunction "G_3") (pintype "passive"))
      (node (ref "U5") (pin "4") (pinfunction "4_4") (pintype "passive"))
    )
    (net (code "36") (name "Net-(D9-A)") (class "Default")
      (node (ref "D9") (pin "2") (pinfunction "A_2") (pintype "passive"))
      (node (ref "K1") (pin "A1") (pinfunction "1_A1") (pintype "passive"))
      (node (ref "Q1") (pin "3") (pinfunction "C_3") (pintype "passive"))
    )
    (net (code "37") (name "Net-(D10-A)") (class "Default")
      (node (ref "D10") (pin "1") (pinfunction "A_1") (pintype "passive"))
      (node (ref "R24") (pin "1") (pinfunction "1_1") (pintype "passive"))
    )
    (net (code "38") (name "Net-(D11-A)") (class "Default")
      (node (ref "D11") (pin "1") (pinfunction "A_1") (pintype "passive"))
      (node (ref "D13") (pin "2") (pinfunction "K_2") (pintype "passive"))
      (node (ref "P10") (pin "1") (pinfunction "1_1") (pintype "passive"))
    )
    (net (code "39") (name "Net-(D12-A)") (class "Default")
      (node (ref "D12") (pin "1") (pinfunction "A_1") (pintype "passive"))
      (node (ref "D14") (pin "2") (pinfunction "K_2") (pintype "passive"))
      (node (ref "P9") (pin "1") (pinfunction "1_1") (pintype "passive"))
    )
    (net (code "40") (name "Net-(F1-Pad2)") (class "Default")
      (node (ref "F1") (pin "2") (pinfunction "2_2") (pintype "passive"))
      (node (ref "P6") (pin "1") (pinfunction "1_1") (pintype "passive"))
    )
    (net (code "41") (name "Net-(F2-Pad2)") (class "Default")
      (node (ref "F2") (pin "2") (pinfunction "2_2") (pintype "passive"))
      (node (ref "P6") (pin "3") (pinfunction "3_3") (pintype "passive"))
    )
    (net (code "42") (name "Net-(Q1-B)") (class "Default")
      (node (ref "Q1") (pin "1") (pinfunction "B_1") (pintype "passive"))
      (node (ref "R21") (pin "2") (pinfunction "2_2") (pintype "passive"))
      (node (ref "R22") (pin "2") (pinfunction "2_2") (pintype "passive"))
    )
    (net (code "43") (name "Net-(Q2-D)") (class "Default")
      (node (ref "Q2") (pin "3") (pinfunction "D_3") (pintype "passive"))
      (node (ref "R25") (pin "2") (pinfunction "2_2") (pintype "passive"))
      (node (ref "R26") (pin "1") (pinfunction "1_1") (pintype "passive"))
    )
    (net (code "44") (name "Net-(R4-Pad2)") (class "Default")
      (node (ref "R4") (pin "2") (pinfunction "2_2") (pintype "passive"))
      (node (ref "R5") (pin "1") (pinfunction "1_1") (pintype "passive"))
    )
    (net (code "45") (name "Net-(R5-Pad2)") (class "Default")
      (node (ref "R5") (pin "2") (pinfunction "2_2") (pintype "passive"))
      (node (ref "R6") (pin "1") (pinfunction "1_1") (pintype "passive"))
    )
    (net (code "46") (name "Net-(R8-Pad2)") (class "Default")
      (node (ref "R8") (pin "2") (pinfunction "2_2") (pintype "passive"))
      (node (ref "R9") (pin "1") (pinfunction "1_1") (pintype "passive"))
    )
    (net (code "47") (name "Net-(R10-Pad1)") (class "Default")
      (node (ref "R10") (pin "1") (pinfunction "1_1") (pintype "passive"))
      (node (ref "R9") (pin "2") (pinfunction "2_2") (pintype "passive"))
    )
    (net (code "48") (name "Net-(R16-Pad2)") (class "Default")
      (node (ref "R16") (pin "2") (pinfunction "2_2") (pintype "passive"))
      (node (ref "R17") (pin "1") (pinfunction "1_1") (pintype "passive"))
    )
    (net (code "49") (name "Net-(R17-Pad2)") (class "Default")
      (node (ref "R17") (pin "2") (pinfunction "2_2") (pintype "passive"))
      (node (ref "R18") (pin "1") (pinfunction "1_1") (pintype "passive"))
    )
    (net (code "50") (name "Net-(R18-Pad2)") (class "Default")
      (node (ref "R18") (pin "2") (pinfunction "2_2") (pintype "passive"))
      (node (ref "U5") (pin "6") (pinfunction "6_6") (pintype "passive"))
    )
    (net (code "51") (name "Net-(R19-Pad2)") (class "Default")
      (node (ref "R19") (pin "2") (pinfunction "2_2") (pintype "passive"))
      (node (ref "U5") (pin "1") (pinfunction "1_1") (pintype "passive"))
    )
    (net (code "52") (name "Net-(S1-A1)") (class "Default")
      (node (ref "R23") (pin "1") (pinfunction "1_1") (pintype "passive"))
      (node (ref "S1") (pin "1") (pinfunction "A1_1") (pintype "passive"))
    )
    (net (code "53") (name "Net-(U1-A)") (class "Default")
      (node (ref "R1") (pin "1") (pinfunction "1_1") (pintype "passive"))
      (node (ref "U1") (pin "1") (pinfunction "A_1") (pintype "passive"))
    )
    (net (code "54") (name "Net-(U1-K)") (class "Default")
      (node (ref "U1") (pin "2") (pinfunction "K_2") (pintype "passive"))
      (node (ref "U2") (pin "1") (pinfunction "OUTA_1") (pintype "output"))
    )
    (net (code "55") (name "Net-(U2A-INA+)") (class "Default")
      (node (ref "R14") (pin "2") (pinfunction "2_2") (pintype "passive"))
      (node (ref "R2") (pin "1") (pinfunction "1_1") (pintype "passive"))
      (node (ref "U2") (pin "3") (pinfunction "INA+_3") (pintype "input"))
    )
    (net (code "56") (name "Net-(U3-A)") (class "Default")
      (node (ref "R11") (pin "2") (pinfunction "2_2") (pintype "passive"))
      (node (ref "U3") (pin "6") (pinfunction "A_6") (pintype "bidirectional"))
      (node (ref "U4") (pin "1") (pinfunction "IO1_1") (pintype "passive"))
    )
    (net (code "57") (name "Net-(U3-R)") (class "Default")
      (node (ref "R13") (pin "1") (pinfunction "1_1") (pintype "passive"))
      (node (ref "U3") (pin "1") (pinfunction "R_1") (pintype "tri_state"))
    )
    (net (code "58") (name "Net-(U3-~{B})") (class "Default")
      (node (ref "R12") (pin "2") (pinfunction "2_2") (pintype "passive"))
      (node (ref "U3") (pin "7") (pinfunction "~{B}_7") (pintype "bidirectional"))
      (node (ref "U4") (pin "2") (pinfunction "IO2_2") (pintype "passive"))
    )
    (net (code "59") (name "Net-(U6-NRST)") (class "Default")
      (node (ref "R20") (pin "2") (pinfunction "2_2") (pintype "passive"))
      (node (ref "U6") (pin "4") (pinfunction "NRST_4") (pintype "bidirectional"))
      (node (ref "U7") (pin "2") (pinfunction "~{RESET}_2") (pintype "open_collector"))
    )
    (net (code "60") (name "Net-(U6-VDDA)") (class "Default")
      (node (ref "C5") (pin "2") (pinfunction "2_2") (pintype "passive"))
      (node (ref "C6") (pin "2") (pinfunction "2_2") (pintype "passive"))
      (node (ref "L1") (pin "2") (pinfunction "2_2") (pintype "passive"))
      (node (ref "U6") (pin "5") (pinfunction "VDDA_5") (pintype "power_in"))
    )
    (net (code "61") (name "Net-(U8-BST)") (class "Default")
      (node (ref "C7") (pin "2") (pinfunction "2_2") (pintype "passive"))
      (node (ref "U8") (pin "6") (pinfunction "BST_6") (pintype "passive"))
    )
    (net (code "62") (name "Net-(U8-SW)") (class "Default")
      (node (ref "C7") (pin "1") (pinfunction "1_1") (pintype "passive"))
      (node (ref "L2") (pin "2") (pinfunction "2_2") (pintype "passive"))
      (node (ref "U8") (pin "5") (pinfunction "SW_5") (pintype "passive"))
    )
    (net (code "63") (name "unconnected-(K1-5-Pad12)") (class "Default")
      (node (ref "K1") (pin "12") (pinfunction "5_12") (pintype "passive"))
    )
    (net (code "64") (name "unconnected-(K1-5-Pad22)") (class "Default")
      (node (ref "K1") (pin "22") (pinfunction "5_22") (pintype "passive"))
    )
    (net (code "65") (name "unconnected-(U2B-GND-Pad4)") (class "Default")
      (node (ref "U2") (pin "4") (pinfunction "GND_4") (pintype "power_in"))
    )
    (net (code "66") (name "unconnected-(U2B-OUTB-Pad7)") (class "Default")
      (node (ref "U2") (pin "7") (pinfunction "OUTB_7") (pintype "output"))
    )
    (net (code "67") (name "unconnected-(U2B-V+-Pad8)") (class "Default")
      (node (ref "U2") (pin "8") (pinfunction "V+_8") (pintype "power_in"))
    )
    (net (code "68") (name "unconnected-(U5-Pad3)") (class "Default")
      (node (ref "U5") (pin "3") (pinfunction "3_3") (pintype "passive"))
    )
    (net (code "69") (name "unconnected-(U5-Pad5)") (class "Default")
      (node (ref "U5") (pin "5") (pinfunction "5_5") (pintype "passive"))
    )
  )
)
